# X_SOLAR_PANEL.net
KiCad netlist of a schematic drawn in EAGLE
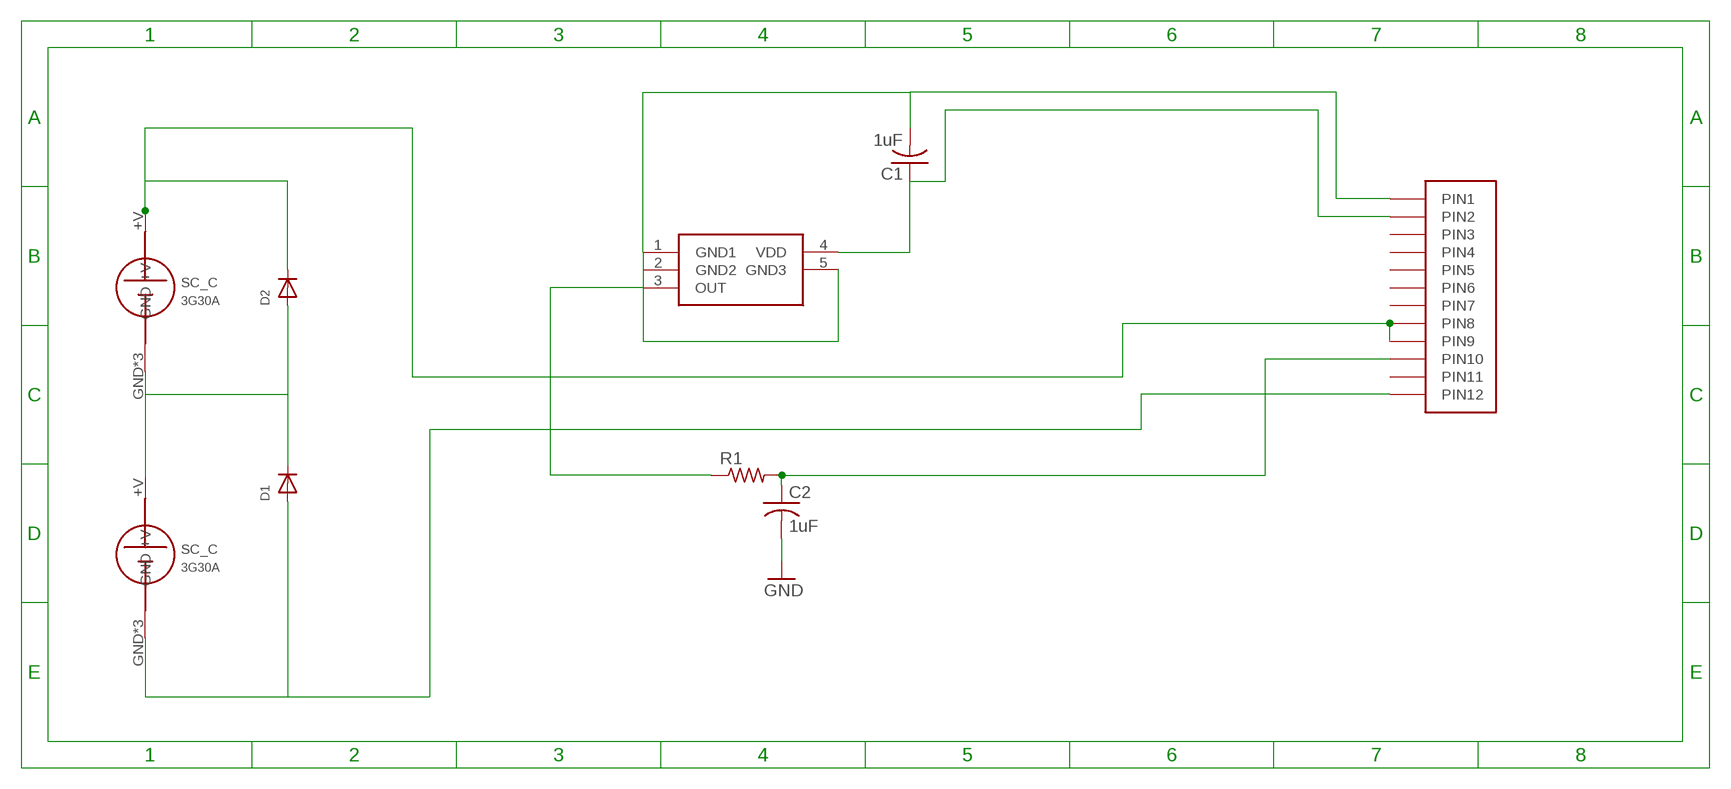
[diagram p0: schematic, sheet 1]

(export (version "E")
  (design (tool "Eeschema 10.0.6"))
  (components
    (comp (ref "C1")
      (value "1uF")
      (footprint "eagle-import:C0805")
      (libsource (lib "eagle-import") (part "C-USC0805"))
    )
    (comp (ref "C2")
      (value "1uF")
      (footprint "eagle-import:C0805")
      (libsource (lib "eagle-import") (part "C-USC0805"))
    )
    (comp (ref "D1")
      (value "DIODE_SOD-123FL")
      (footprint "eagle-import:SOD-123FL")
      (libsource (lib "eagle-import") (part "DIODE_SOD-123FL"))
    )
    (comp (ref "D2")
      (value "DIODE_SOD-123FL")
      (footprint "eagle-import:SOD-123FL")
      (libsource (lib "eagle-import") (part "DIODE_SOD-123FL"))
    )
    (comp (ref "R1")
      (value "R-US_R0402")
      (footprint "eagle-import:R0402")
      (libsource (lib "eagle-import") (part "R-US_R0402"))
    )
    (comp (ref "U$1")
      (value "HEADER12PIN")
      (footprint "eagle-import:HEADER12PIN")
      (libsource (lib "eagle-import") (part "HEADER12PIN"))
    )
    (comp (ref "U$3")
      (value "LMT84DCKT")
      (footprint "eagle-import:SOT65P210X110-5N")
      (fields (field (name "RS_PART_NUMBER") "8115860"))
      (libsource (lib "eagle-import") (part "LMT84DCKT"))
    )
    (comp (ref "U$4")
      (value "SC_C")
      (footprint "eagle-import:SC_C")
      (libsource (lib "eagle-import") (part "SC_C"))
    )
    (comp (ref "U$5")
      (value "SC_C")
      (footprint "eagle-import:SC_C")
      (libsource (lib "eagle-import") (part "SC_C"))
    )
  )
  (nets
    (net (code "1") (name "GND") (class "Default")
      (node (ref "C1") (pin "2") (pinfunction "2_2") (pintype "passive"))
      (node (ref "C2") (pin "2") (pinfunction "2_2") (pintype "passive"))
      (node (ref "D1") (pin "A") (pinfunction "A_A") (pintype "passive"))
      (node (ref "U$1") (pin "P1") (pinfunction "PIN1_P1") (pintype "bidirectional"))
      (node (ref "U$1") (pin "P12") (pinfunction "PIN12_P12") (pintype "bidirectional"))
      (node (ref "U$3") (pin "1") (pinfunction "GND1_1") (pintype "power_in"))
      (node (ref "U$3") (pin "2") (pinfunction "GND2_2") (pintype "power_in"))
      (node (ref "U$3") (pin "5") (pinfunction "GND3_5") (pintype "power_in"))
      (node (ref "U$5") (pin "GND") (pinfunction "GND_GND") (pintype "bidirectional"))
      (node (ref "U$5") (pin "GND1") (pinfunction "GND_GND1") (pintype "bidirectional"))
      (node (ref "U$5") (pin "GND2") (pinfunction "GND_GND2") (pintype "bidirectional"))
    )
    (net (code "2") (name "Net-(D1-PadC)") (class "Default")
      (node (ref "D1") (pin "C") (pinfunction "C_C") (pintype "passive"))
      (node (ref "D2") (pin "A") (pinfunction "A_A") (pintype "passive"))
      (node (ref "U$4") (pin "GND") (pinfunction "GND_GND") (pintype "bidirectional"))
      (node (ref "U$4") (pin "GND1") (pinfunction "GND_GND1") (pintype "bidirectional"))
      (node (ref "U$4") (pin "GND2") (pinfunction "GND_GND2") (pintype "bidirectional"))
      (node (ref "U$5") (pin "+V") (pinfunction "+V_+V") (pintype "bidirectional"))
    )
    (net (code "3") (name "Net-(U$1-PIN2)") (class "Default")
      (node (ref "C1") (pin "1") (pinfunction "1_1") (pintype "passive"))
      (node (ref "U$1") (pin "P2") (pinfunction "PIN2_P2") (pintype "bidirectional"))
      (node (ref "U$3") (pin "4") (pinfunction "VDD_4") (pintype "power_in"))
    )
    (net (code "4") (name "Net-(U$1-PIN8)") (class "Default")
      (node (ref "D2") (pin "C") (pinfunction "C_C") (pintype "passive"))
      (node (ref "U$1") (pin "P8") (pinfunction "PIN8_P8") (pintype "bidirectional"))
      (node (ref "U$1") (pin "P9") (pinfunction "PIN9_P9") (pintype "bidirectional"))
      (node (ref "U$4") (pin "+V") (pinfunction "+V_+V") (pintype "bidirectional"))
    )
    (net (code "5") (name "Net-(U$1-PIN10)") (class "Default")
      (node (ref "C2") (pin "1") (pinfunction "1_1") (pintype "passive"))
      (node (ref "R1") (pin "2") (pinfunction "2_2") (pintype "passive"))
      (node (ref "U$1") (pin "P10") (pinfunction "PIN10_P10") (pintype "bidirectional"))
    )
    (net (code "6") (name "Net-(U$3-OUT)") (class "Default")
      (node (ref "R1") (pin "1") (pinfunction "1_1") (pintype "passive"))
      (node (ref "U$3") (pin "3") (pinfunction "OUT_3") (pintype "output"))
    )
    (net (code "7") (name "unconnected-(U$1-PIN3-PadP3)") (class "Default")
      (node (ref "U$1") (pin "P3") (pinfunction "PIN3_P3") (pintype "bidirectional"))
    )
    (net (code "8") (name "unconnected-(U$1-PIN4-PadP4)") (class "Default")
      (node (ref "U$1") (pin "P4") (pinfunction "PIN4_P4") (pintype "bidirectional"))
    )
    (net (code "9") (name "unconnected-(U$1-PIN5-PadP5)") (class "Default")
      (node (ref "U$1") (pin "P5") (pinfunction "PIN5_P5") (pintype "bidirectional"))
    )
    (net (code "10") (name "unconnected-(U$1-PIN6-PadP6)") (class "Default")
      (node (ref "U$1") (pin "P6") (pinfunction "PIN6_P6") (pintype "bidirectional"))
    )
    (net (code "11") (name "unconnected-(U$1-PIN7-PadP7)") (class "Default")
      (node (ref "U$1") (pin "P7") (pinfunction "PIN7_P7") (pintype "bidirectional"))
    )
    (net (code "12") (name "unconnected-(U$1-PIN11-PadP11)") (class "Default")
      (node (ref "U$1") (pin "P11") (pinfunction "PIN11_P11") (pintype "bidirectional"))
    )
  )
)
